# Adafruit_LTR390.net
KiCad netlist of a schematic drawn in EAGLE
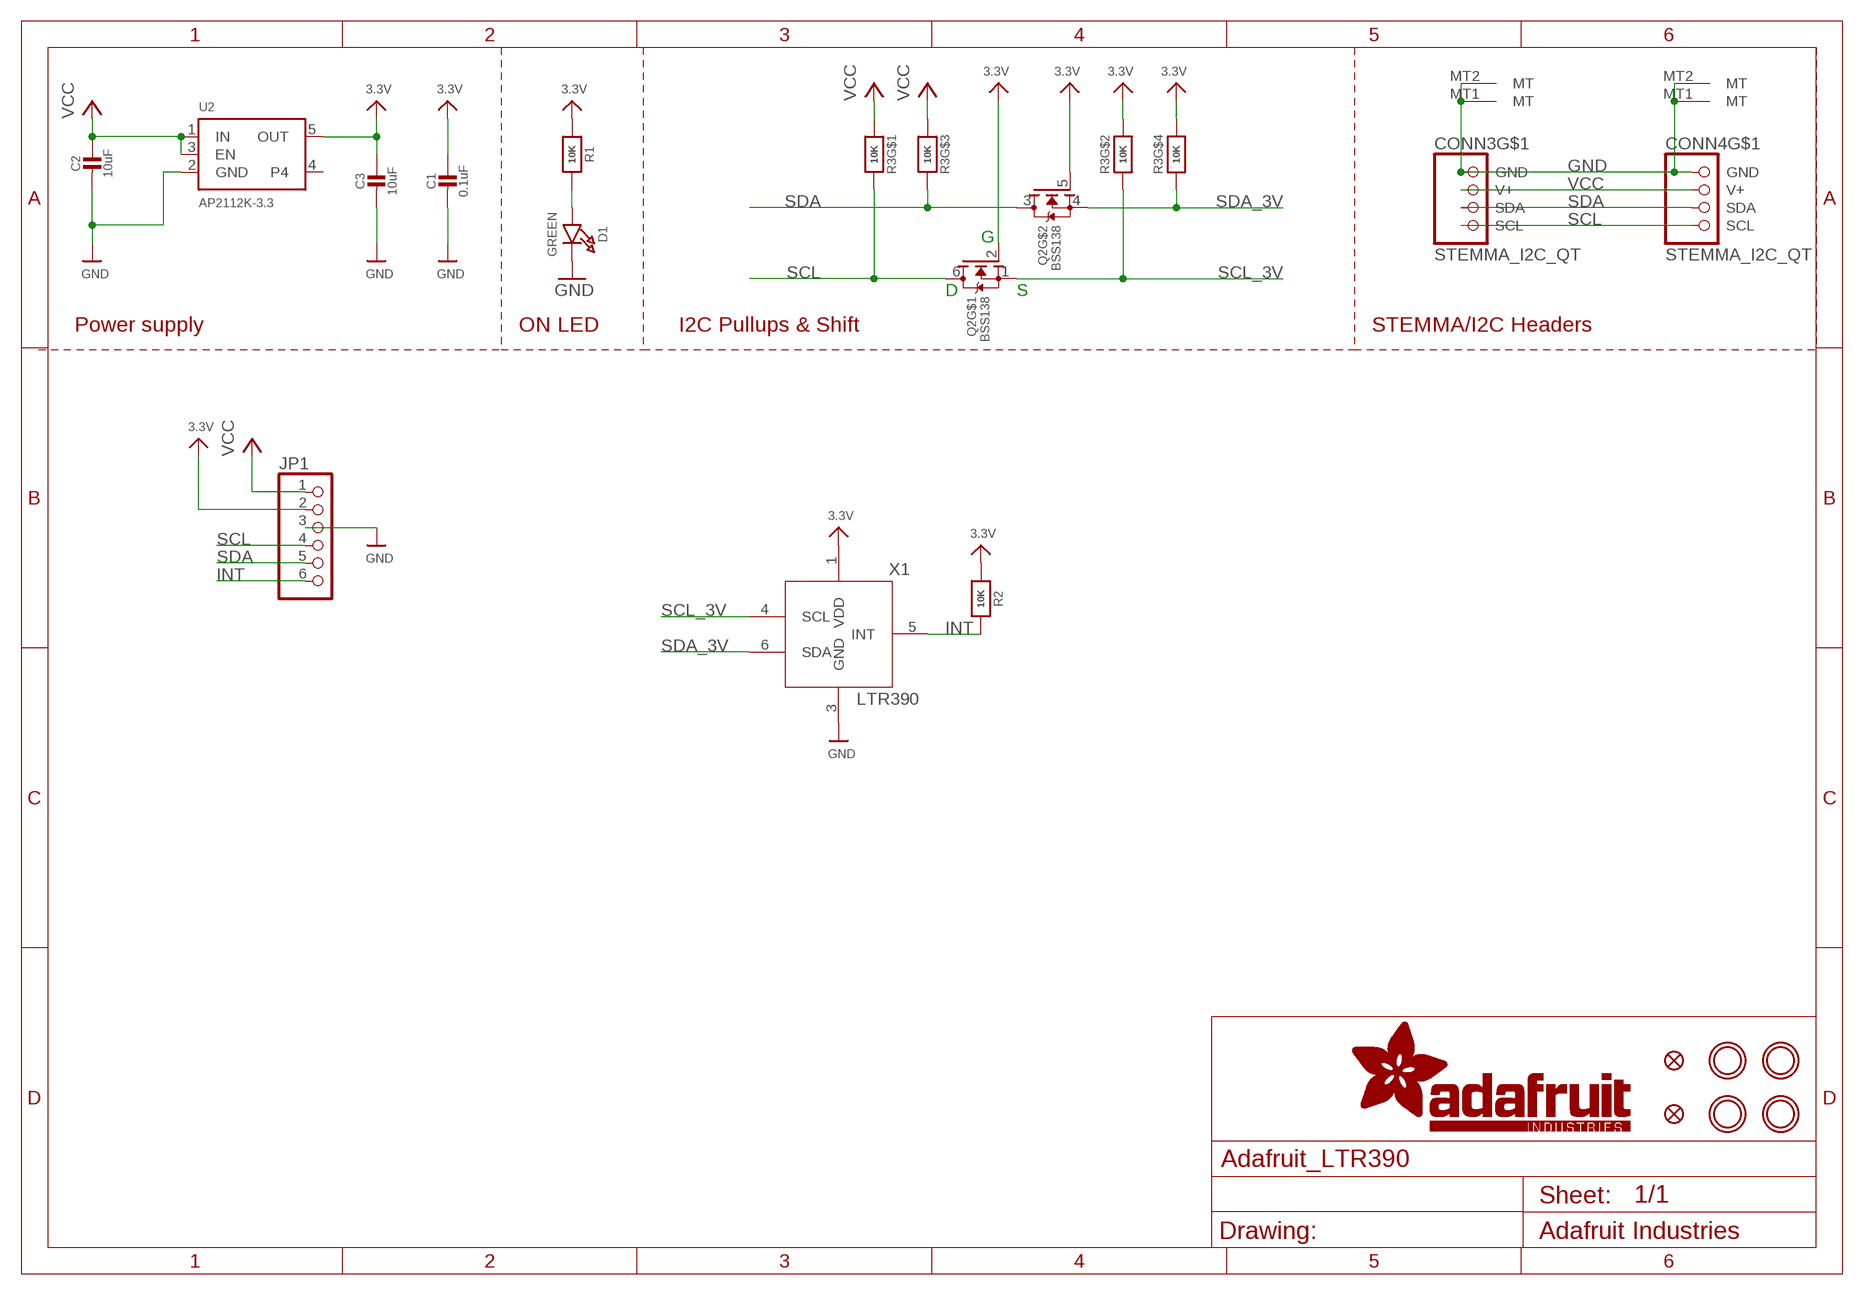
[diagram p0: schematic, sheet 1]

(export (version "E")
  (design (tool "Eeschema 10.0.6"))
  (components
    (comp (ref "C1")
      (value "0.1uF")
      (footprint "eagle-import:0603-NO")
      (libsource (lib "eagle-import") (part "CAP_CERAMIC0603_NO"))
    )
    (comp (ref "C2")
      (value "10uF")
      (footprint "eagle-import:0805-NO")
      (libsource (lib "eagle-import") (part "CAP_CERAMIC0805-NOOUTLINE"))
    )
    (comp (ref "C3")
      (value "10uF")
      (footprint "eagle-import:0805-NO")
      (libsource (lib "eagle-import") (part "CAP_CERAMIC0805-NOOUTLINE"))
    )
    (comp (ref "CONN3")
      (value "STEMMA_I2C_QT")
      (footprint "eagle-import:JST_SH4")
      (libsource (lib "eagle-import") (part "STEMMA_I2C_QT"))
    )
    (comp (ref "CONN4")
      (value "STEMMA_I2C_QT")
      (footprint "eagle-import:JST_SH4")
      (libsource (lib "eagle-import") (part "STEMMA_I2C_QT"))
    )
    (comp (ref "D1")
      (value "GREEN")
      (footprint "eagle-import:CHIPLED_0603_NOOUTLINE")
      (libsource (lib "eagle-import") (part "LED0603_NOOUTLINE"))
    )
    (comp (ref "FID3")
      (value "FIDUCIAL_1MM")
      (footprint "eagle-import:FIDUCIAL_1MM")
      (libsource (lib "eagle-import") (part "FIDUCIAL_1MM"))
    )
    (comp (ref "FID4")
      (value "FIDUCIAL_1MM")
      (footprint "eagle-import:FIDUCIAL_1MM")
      (libsource (lib "eagle-import") (part "FIDUCIAL_1MM"))
    )
    (comp (ref "JP1")
      (value "HEADER-1X670MIL")
      (footprint "eagle-import:1X06_ROUND_70")
      (libsource (lib "eagle-import") (part "HEADER-1X670MIL"))
    )
    (comp (ref "Q2")
      (value "BSS138")
      (footprint "eagle-import:SOT363")
      (libsource (lib "eagle-import") (part "MOSFET-N_DUAL"))
    )
    (comp (ref "R1")
      (value "10K")
      (footprint "eagle-import:0603-NO")
      (libsource (lib "eagle-import") (part "RESISTOR_0603_NOOUT"))
    )
    (comp (ref "R2")
      (value "10K")
      (footprint "eagle-import:0603-NO")
      (libsource (lib "eagle-import") (part "RESISTOR_0603_NOOUT"))
    )
    (comp (ref "R3")
      (value "10K")
      (footprint "eagle-import:RESPACK_4X0603")
      (libsource (lib "eagle-import") (part "RESISTOR_4PACK"))
    )
    (comp (ref "U$1")
      (value "MOUNTINGHOLE2.5")
      (footprint "eagle-import:MOUNTINGHOLE_2.5_PLATED")
      (libsource (lib "eagle-import") (part "MOUNTINGHOLE2.5"))
    )
    (comp (ref "U$17")
      (value "MOUNTINGHOLE2.5")
      (footprint "eagle-import:MOUNTINGHOLE_2.5_PLATED")
      (libsource (lib "eagle-import") (part "MOUNTINGHOLE2.5"))
    )
    (comp (ref "U$19")
      (value "MOUNTINGHOLE2.5")
      (footprint "eagle-import:MOUNTINGHOLE_2.5_PLATED")
      (libsource (lib "eagle-import") (part "MOUNTINGHOLE2.5"))
    )
    (comp (ref "U$21")
      (value "MOUNTINGHOLE2.5")
      (footprint "eagle-import:MOUNTINGHOLE_2.5_PLATED")
      (libsource (lib "eagle-import") (part "MOUNTINGHOLE2.5"))
    )
    (comp (ref "U2")
      (value "AP2112K-3.3")
      (footprint "eagle-import:SOT23-5")
      (libsource (lib "eagle-import") (part "VREG_SOT23-5"))
    )
    (comp (ref "X1")
      (value "LTR390")
      (footprint "eagle-import:LTR390")
      (libsource (lib "eagle-import") (part "LTR390"))
    )
  )
  (nets
    (net (code "1") (name "/INT") (class "Default")
      (node (ref "JP1") (pin "6") (pinfunction "6_6") (pintype "passive"))
      (node (ref "R2") (pin "2") (pinfunction "2_2") (pintype "passive"))
      (node (ref "X1") (pin "5") (pinfunction "INT_5") (pintype "bidirectional"))
    )
    (net (code "2") (name "/SCL") (class "Default")
      (node (ref "CONN3") (pin "4") (pinfunction "SCL_4") (pintype "passive"))
      (node (ref "CONN4") (pin "4") (pinfunction "SCL_4") (pintype "passive"))
      (node (ref "JP1") (pin "4") (pinfunction "4_4") (pintype "passive"))
      (node (ref "Q2") (pin "6") (pinfunction "D_6") (pintype "bidirectional"))
      (node (ref "R3") (pin "8") (pinfunction "2_8") (pintype "passive"))
    )
    (net (code "3") (name "/SCL_3V") (class "Default")
      (node (ref "Q2") (pin "1") (pinfunction "S_1") (pintype "bidirectional"))
      (node (ref "R3") (pin "7") (pinfunction "2_7") (pintype "passive"))
      (node (ref "X1") (pin "4") (pinfunction "SCL_4") (pintype "bidirectional"))
    )
    (net (code "4") (name "/SDA") (class "Default")
      (node (ref "CONN3") (pin "3") (pinfunction "SDA_3") (pintype "passive"))
      (node (ref "CONN4") (pin "3") (pinfunction "SDA_3") (pintype "passive"))
      (node (ref "JP1") (pin "5") (pinfunction "5_5") (pintype "passive"))
      (node (ref "Q2") (pin "3") (pinfunction "D_3") (pintype "bidirectional"))
      (node (ref "R3") (pin "6") (pinfunction "2_6") (pintype "passive"))
    )
    (net (code "5") (name "/SDA_3V") (class "Default")
      (node (ref "Q2") (pin "4") (pinfunction "S_4") (pintype "bidirectional"))
      (node (ref "R3") (pin "5") (pinfunction "2_5") (pintype "passive"))
      (node (ref "X1") (pin "6") (pinfunction "SDA_6") (pintype "bidirectional"))
    )
    (net (code "6") (name "3.3V") (class "Default")
      (node (ref "C1") (pin "1") (pinfunction "1_1") (pintype "passive"))
      (node (ref "C3") (pin "1") (pinfunction "1_1") (pintype "passive"))
      (node (ref "JP1") (pin "2") (pinfunction "2_2") (pintype "passive"))
      (node (ref "Q2") (pin "2") (pinfunction "G_2") (pintype "bidirectional"))
      (node (ref "Q2") (pin "5") (pinfunction "G_5") (pintype "bidirectional"))
      (node (ref "R1") (pin "1") (pinfunction "1_1") (pintype "passive"))
      (node (ref "R2") (pin "1") (pinfunction "1_1") (pintype "passive"))
      (node (ref "R3") (pin "2") (pinfunction "1_2") (pintype "passive"))
      (node (ref "R3") (pin "4") (pinfunction "1_4") (pintype "passive"))
      (node (ref "U2") (pin "5") (pinfunction "OUT_5") (pintype "power_in"))
      (node (ref "X1") (pin "1") (pinfunction "VDD_1") (pintype "power_in"))
    )
    (net (code "7") (name "GND") (class "Default")
      (node (ref "C1") (pin "2") (pinfunction "2_2") (pintype "passive"))
      (node (ref "C2") (pin "2") (pinfunction "2_2") (pintype "passive"))
      (node (ref "C3") (pin "2") (pinfunction "2_2") (pintype "passive"))
      (node (ref "CONN3") (pin "1") (pinfunction "GND_1") (pintype "passive"))
      (node (ref "CONN3") (pin "MT1") (pinfunction "MT_MT1") (pintype "bidirectional"))
      (node (ref "CONN3") (pin "MT2") (pinfunction "MT_MT2") (pintype "bidirectional"))
      (node (ref "CONN4") (pin "1") (pinfunction "GND_1") (pintype "passive"))
      (node (ref "CONN4") (pin "MT1") (pinfunction "MT_MT1") (pintype "bidirectional"))
      (node (ref "CONN4") (pin "MT2") (pinfunction "MT_MT2") (pintype "bidirectional"))
      (node (ref "D1") (pin "C") (pinfunction "C_C") (pintype "passive"))
      (node (ref "JP1") (pin "3") (pinfunction "3_3") (pintype "passive"))
      (node (ref "U2") (pin "2") (pinfunction "GND_2") (pintype "power_in"))
      (node (ref "X1") (pin "3") (pinfunction "GND_3") (pintype "power_in"))
    )
    (net (code "8") (name "Net-(D1-PadA)") (class "Default")
      (node (ref "D1") (pin "A") (pinfunction "A_A") (pintype "passive"))
      (node (ref "R1") (pin "2") (pinfunction "2_2") (pintype "passive"))
    )
    (net (code "9") (name "VCC") (class "Default")
      (node (ref "C2") (pin "1") (pinfunction "1_1") (pintype "passive"))
      (node (ref "CONN3") (pin "2") (pinfunction "V+_2") (pintype "passive"))
      (node (ref "CONN4") (pin "2") (pinfunction "V+_2") (pintype "passive"))
      (node (ref "JP1") (pin "1") (pinfunction "1_1") (pintype "passive"))
      (node (ref "R3") (pin "1") (pinfunction "1_1") (pintype "passive"))
      (node (ref "R3") (pin "3") (pinfunction "1_3") (pintype "passive"))
      (node (ref "U2") (pin "1") (pinfunction "IN_1") (pintype "power_in"))
      (node (ref "U2") (pin "3") (pinfunction "EN_3") (pintype "input"))
    )
    (net (code "10") (name "unconnected-(U2-P4-Pad4)") (class "Default")
      (node (ref "U2") (pin "4") (pinfunction "P4_4") (pintype "bidirectional"))
    )
  )
)
